# Filter.net
KiCad netlist of a schematic drawn in EAGLE
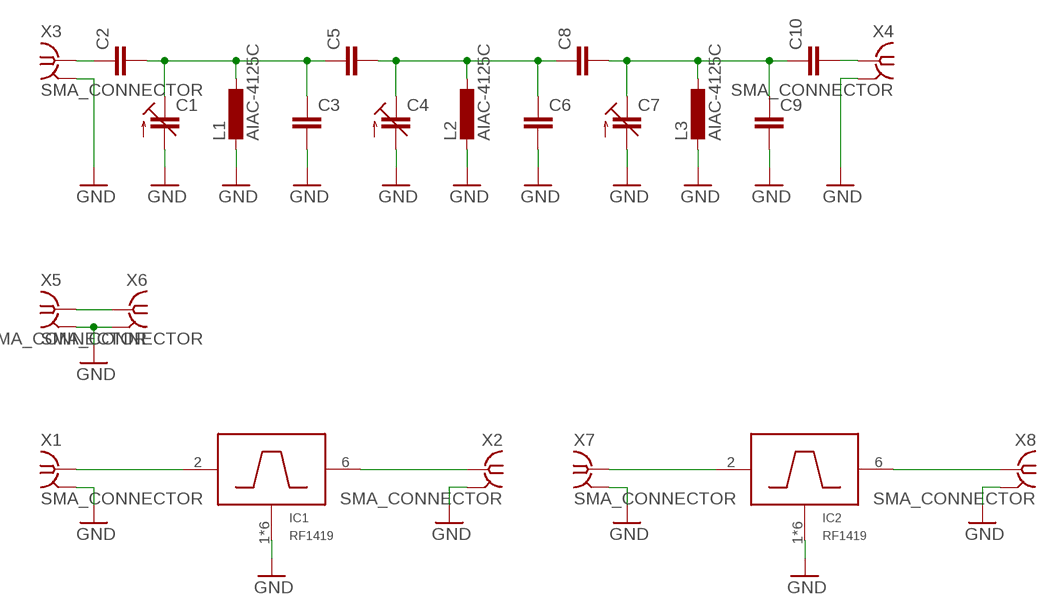
[diagram p0: schematic, sheet 1]

(export (version "E")
  (design (tool "Eeschema 10.0.6"))
  (components
    (comp (ref "C1")
      (value "C-TRIMMCTZ3")
      (footprint "eagle-import:CTRIMCTZ3")
      (libsource (lib "eagle-import") (part "C-TRIMMCTZ3"))
    )
    (comp (ref "C2")
      (value "C-EUC0603")
      (footprint "eagle-import:C0603")
      (libsource (lib "eagle-import") (part "C-EUC0603"))
    )
    (comp (ref "C3")
      (value "C-EUC0603")
      (footprint "eagle-import:C0603")
      (libsource (lib "eagle-import") (part "C-EUC0603"))
    )
    (comp (ref "C4")
      (value "C-TRIMMCTZ3")
      (footprint "eagle-import:CTRIMCTZ3")
      (libsource (lib "eagle-import") (part "C-TRIMMCTZ3"))
    )
    (comp (ref "C5")
      (value "C-EUC0603")
      (footprint "eagle-import:C0603")
      (libsource (lib "eagle-import") (part "C-EUC0603"))
    )
    (comp (ref "C6")
      (value "C-EUC0603")
      (footprint "eagle-import:C0603")
      (libsource (lib "eagle-import") (part "C-EUC0603"))
    )
    (comp (ref "C7")
      (value "C-TRIMMCTZ3")
      (footprint "eagle-import:CTRIMCTZ3")
      (libsource (lib "eagle-import") (part "C-TRIMMCTZ3"))
    )
    (comp (ref "C8")
      (value "C-EUC0603")
      (footprint "eagle-import:C0603")
      (libsource (lib "eagle-import") (part "C-EUC0603"))
    )
    (comp (ref "C9")
      (value "C-EUC0603")
      (footprint "eagle-import:C0603")
      (libsource (lib "eagle-import") (part "C-EUC0603"))
    )
    (comp (ref "C10")
      (value "C-EUC0603")
      (footprint "eagle-import:C0603")
      (libsource (lib "eagle-import") (part "C-EUC0603"))
    )
    (comp (ref "IC1")
      (value "RF1419")
      (footprint "eagle-import:RESCAV127P380X380X120-8")
      (libsource (lib "eagle-import") (part "RF1419"))
    )
    (comp (ref "IC2")
      (value "RF1419")
      (footprint "eagle-import:RESCAV127P380X380X120-8")
      (libsource (lib "eagle-import") (part "RF1419"))
    )
    (comp (ref "L1")
      (value "AIAC-4125C")
      (footprint "eagle-import:AIAC-4125C")
      (libsource (lib "eagle-import") (part "AIAC-4125C"))
    )
    (comp (ref "L2")
      (value "AIAC-4125C")
      (footprint "eagle-import:AIAC-4125C")
      (libsource (lib "eagle-import") (part "AIAC-4125C"))
    )
    (comp (ref "L3")
      (value "AIAC-4125C")
      (footprint "eagle-import:AIAC-4125C")
      (libsource (lib "eagle-import") (part "AIAC-4125C"))
    )
    (comp (ref "X1")
      (value "SMA_CONNECTOR")
      (footprint "eagle-import:J502-ND-142-0711-821_826")
      (libsource (lib "eagle-import") (part "SMA_CONNECTOR"))
    )
    (comp (ref "X2")
      (value "SMA_CONNECTOR")
      (footprint "eagle-import:J502-ND-142-0711-821_826")
      (libsource (lib "eagle-import") (part "SMA_CONNECTOR"))
    )
    (comp (ref "X3")
      (value "SMA_CONNECTOR")
      (footprint "eagle-import:J502-ND-142-0711-821_826")
      (libsource (lib "eagle-import") (part "SMA_CONNECTOR"))
    )
    (comp (ref "X4")
      (value "SMA_CONNECTOR")
      (footprint "eagle-import:J502-ND-142-0711-821_826")
      (libsource (lib "eagle-import") (part "SMA_CONNECTOR"))
    )
    (comp (ref "X5")
      (value "SMA_CONNECTOR")
      (footprint "eagle-import:J502-ND-142-0711-821_826")
      (libsource (lib "eagle-import") (part "SMA_CONNECTOR"))
    )
    (comp (ref "X6")
      (value "SMA_CONNECTOR")
      (footprint "eagle-import:J502-ND-142-0711-821_826")
      (libsource (lib "eagle-import") (part "SMA_CONNECTOR"))
    )
    (comp (ref "X7")
      (value "SMA_CONNECTOR")
      (footprint "eagle-import:J502-ND-142-0711-821_826")
      (libsource (lib "eagle-import") (part "SMA_CONNECTOR"))
    )
    (comp (ref "X8")
      (value "SMA_CONNECTOR")
      (footprint "eagle-import:J502-ND-142-0711-821_826")
      (libsource (lib "eagle-import") (part "SMA_CONNECTOR"))
    )
  )
  (nets
    (net (code "1") (name "GND") (class "Default")
      (node (ref "C1") (pin "2") (pinfunction "A_2") (pintype "passive"))
      (node (ref "C3") (pin "2") (pinfunction "2_2") (pintype "passive"))
      (node (ref "C4") (pin "2") (pinfunction "A_2") (pintype "passive"))
      (node (ref "C6") (pin "2") (pinfunction "2_2") (pintype "passive"))
      (node (ref "C7") (pin "2") (pinfunction "A_2") (pintype "passive"))
      (node (ref "C9") (pin "2") (pinfunction "2_2") (pintype "passive"))
      (node (ref "IC1") (pin "1") (pinfunction "GND_1") (pintype "bidirectional"))
      (node (ref "IC1") (pin "3") (pinfunction "GND_3") (pintype "bidirectional"))
      (node (ref "IC1") (pin "4") (pinfunction "GND_4") (pintype "bidirectional"))
      (node (ref "IC1") (pin "5") (pinfunction "GND_5") (pintype "bidirectional"))
      (node (ref "IC1") (pin "7") (pinfunction "GND_7") (pintype "bidirectional"))
      (node (ref "IC1") (pin "8") (pinfunction "GND_8") (pintype "bidirectional"))
      (node (ref "IC2") (pin "1") (pinfunction "GND_1") (pintype "bidirectional"))
      (node (ref "IC2") (pin "3") (pinfunction "GND_3") (pintype "bidirectional"))
      (node (ref "IC2") (pin "4") (pinfunction "GND_4") (pintype "bidirectional"))
      (node (ref "IC2") (pin "5") (pinfunction "GND_5") (pintype "bidirectional"))
      (node (ref "IC2") (pin "7") (pinfunction "GND_7") (pintype "bidirectional"))
      (node (ref "IC2") (pin "8") (pinfunction "GND_8") (pintype "bidirectional"))
      (node (ref "L1") (pin "P$2") (pinfunction "2_P$2") (pintype "passive"))
      (node (ref "L2") (pin "P$2") (pinfunction "2_P$2") (pintype "passive"))
      (node (ref "L3") (pin "P$2") (pinfunction "2_P$2") (pintype "passive"))
      (node (ref "X1") (pin "G@1") (pinfunction "2_G@1") (pintype "passive"))
      (node (ref "X1") (pin "G@2") (pinfunction "2_G@2") (pintype "passive"))
      (node (ref "X1") (pin "G@3") (pinfunction "2_G@3") (pintype "passive"))
      (node (ref "X1") (pin "G@4") (pinfunction "2_G@4") (pintype "passive"))
      (node (ref "X2") (pin "G@1") (pinfunction "2_G@1") (pintype "passive"))
      (node (ref "X2") (pin "G@2") (pinfunction "2_G@2") (pintype "passive"))
      (node (ref "X2") (pin "G@3") (pinfunction "2_G@3") (pintype "passive"))
      (node (ref "X2") (pin "G@4") (pinfunction "2_G@4") (pintype "passive"))
      (node (ref "X3") (pin "G@1") (pinfunction "2_G@1") (pintype "passive"))
      (node (ref "X3") (pin "G@2") (pinfunction "2_G@2") (pintype "passive"))
      (node (ref "X3") (pin "G@3") (pinfunction "2_G@3") (pintype "passive"))
      (node (ref "X3") (pin "G@4") (pinfunction "2_G@4") (pintype "passive"))
      (node (ref "X4") (pin "G@1") (pinfunction "2_G@1") (pintype "passive"))
      (node (ref "X4") (pin "G@2") (pinfunction "2_G@2") (pintype "passive"))
      (node (ref "X4") (pin "G@3") (pinfunction "2_G@3") (pintype "passive"))
      (node (ref "X4") (pin "G@4") (pinfunction "2_G@4") (pintype "passive"))
      (node (ref "X5") (pin "G@1") (pinfunction "2_G@1") (pintype "passive"))
      (node (ref "X5") (pin "G@2") (pinfunction "2_G@2") (pintype "passive"))
      (node (ref "X5") (pin "G@3") (pinfunction "2_G@3") (pintype "passive"))
      (node (ref "X5") (pin "G@4") (pinfunction "2_G@4") (pintype "passive"))
      (node (ref "X6") (pin "G@1") (pinfunction "2_G@1") (pintype "passive"))
      (node (ref "X6") (pin "G@2") (pinfunction "2_G@2") (pintype "passive"))
      (node (ref "X6") (pin "G@3") (pinfunction "2_G@3") (pintype "passive"))
      (node (ref "X6") (pin "G@4") (pinfunction "2_G@4") (pintype "passive"))
      (node (ref "X7") (pin "G@1") (pinfunction "2_G@1") (pintype "passive"))
      (node (ref "X7") (pin "G@2") (pinfunction "2_G@2") (pintype "passive"))
      (node (ref "X7") (pin "G@3") (pinfunction "2_G@3") (pintype "passive"))
      (node (ref "X7") (pin "G@4") (pinfunction "2_G@4") (pintype "passive"))
      (node (ref "X8") (pin "G@1") (pinfunction "2_G@1") (pintype "passive"))
      (node (ref "X8") (pin "G@2") (pinfunction "2_G@2") (pintype "passive"))
      (node (ref "X8") (pin "G@3") (pinfunction "2_G@3") (pintype "passive"))
      (node (ref "X8") (pin "G@4") (pinfunction "2_G@4") (pintype "passive"))
    )
    (net (code "2") (name "Net-(C1-E)") (class "Default")
      (node (ref "C1") (pin "1") (pinfunction "E_1") (pintype "passive"))
      (node (ref "C2") (pin "2") (pinfunction "2_2") (pintype "passive"))
      (node (ref "C3") (pin "1") (pinfunction "1_1") (pintype "passive"))
      (node (ref "C5") (pin "1") (pinfunction "1_1") (pintype "passive"))
      (node (ref "L1") (pin "P$1") (pinfunction "1_P$1") (pintype "passive"))
    )
    (net (code "3") (name "Net-(C2-Pad1)") (class "Default")
      (node (ref "C2") (pin "1") (pinfunction "1_1") (pintype "passive"))
      (node (ref "X3") (pin "1") (pinfunction "1_1") (pintype "passive"))
    )
    (net (code "4") (name "Net-(C4-E)") (class "Default")
      (node (ref "C4") (pin "1") (pinfunction "E_1") (pintype "passive"))
      (node (ref "C5") (pin "2") (pinfunction "2_2") (pintype "passive"))
      (node (ref "C6") (pin "1") (pinfunction "1_1") (pintype "passive"))
      (node (ref "C8") (pin "1") (pinfunction "1_1") (pintype "passive"))
      (node (ref "L2") (pin "P$1") (pinfunction "1_P$1") (pintype "passive"))
    )
    (net (code "5") (name "Net-(C7-E)") (class "Default")
      (node (ref "C10") (pin "1") (pinfunction "1_1") (pintype "passive"))
      (node (ref "C7") (pin "1") (pinfunction "E_1") (pintype "passive"))
      (node (ref "C8") (pin "2") (pinfunction "2_2") (pintype "passive"))
      (node (ref "C9") (pin "1") (pinfunction "1_1") (pintype "passive"))
      (node (ref "L3") (pin "P$1") (pinfunction "1_P$1") (pintype "passive"))
    )
    (net (code "6") (name "Net-(C10-Pad2)") (class "Default")
      (node (ref "C10") (pin "2") (pinfunction "2_2") (pintype "passive"))
      (node (ref "X4") (pin "1") (pinfunction "1_1") (pintype "passive"))
    )
    (net (code "7") (name "Net-(IC1-IN)") (class "Default")
      (node (ref "IC1") (pin "2") (pinfunction "IN_2") (pintype "bidirectional"))
      (node (ref "X1") (pin "1") (pinfunction "1_1") (pintype "passive"))
    )
    (net (code "8") (name "Net-(IC1-OUT)") (class "Default")
      (node (ref "IC1") (pin "6") (pinfunction "OUT_6") (pintype "bidirectional"))
      (node (ref "X2") (pin "1") (pinfunction "1_1") (pintype "passive"))
    )
    (net (code "9") (name "Net-(IC2-IN)") (class "Default")
      (node (ref "IC2") (pin "2") (pinfunction "IN_2") (pintype "bidirectional"))
      (node (ref "X7") (pin "1") (pinfunction "1_1") (pintype "passive"))
    )
    (net (code "10") (name "Net-(IC2-OUT)") (class "Default")
      (node (ref "IC2") (pin "6") (pinfunction "OUT_6") (pintype "bidirectional"))
      (node (ref "X8") (pin "1") (pinfunction "1_1") (pintype "passive"))
    )
    (net (code "11") (name "Net-(X5-Pad1)") (class "Default")
      (node (ref "X5") (pin "1") (pinfunction "1_1") (pintype "passive"))
      (node (ref "X6") (pin "1") (pinfunction "1_1") (pintype "passive"))
    )
  )
)
